# smartControllerDIP.net
KiCad netlist of a schematic drawn in Altium Designer
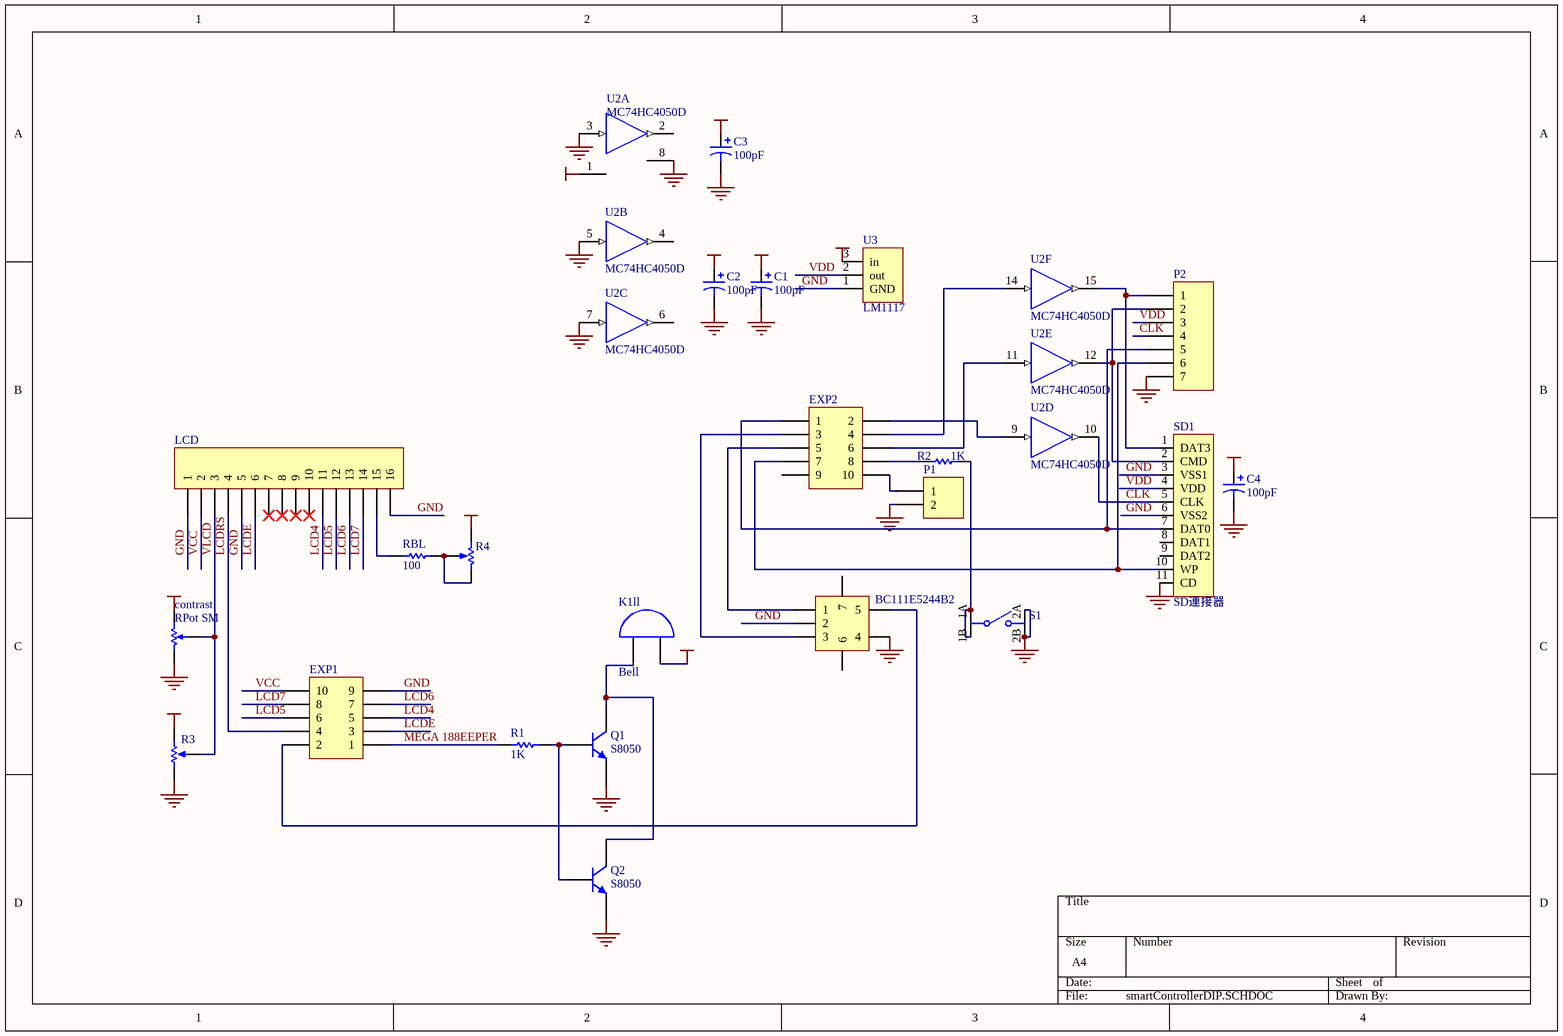
[diagram p0: smartControllerDIP.SCHDOC]

(export (version "E")
  (design (tool "Eeschema 10.0.6"))
  (components
    (comp (ref "BC111E5244B2")
      (value "上下數 編碼器")
      (footprint "上下數 編碼器")
      (libsource (lib "mydata") (part "上下數 編碼器"))
    )
    (comp (ref "C1")
      (value "100pF")
      (footprint "CC2012-0805")
      (description "Polarized Capacitor (Surface Mount)")
      (fields (field (name "Comment") "Cap Pol3") (field (name "PUBLISHER") "Altium Limited"))
      (libsource (lib "Miscellaneous Devices") (part "Cap Pol3"))
    )
    (comp (ref "C2")
      (value "100pF")
      (footprint "CC2012-0805")
      (description "Polarized Capacitor (Surface Mount)")
      (fields (field (name "Comment") "Cap Pol3") (field (name "PUBLISHER") "Altium Limited"))
      (libsource (lib "Miscellaneous Devices") (part "Cap Pol3"))
    )
    (comp (ref "C3")
      (value "100pF")
      (footprint "CC2012-0805")
      (description "Polarized Capacitor (Surface Mount)")
      (fields (field (name "Comment") "Cap Pol3") (field (name "PUBLISHER") "Altium Limited"))
      (libsource (lib "Miscellaneous Devices") (part "Cap Pol3"))
    )
    (comp (ref "C4")
      (value "100pF")
      (footprint "CC2012-0805")
      (description "Polarized Capacitor (Surface Mount)")
      (fields (field (name "Comment") "Cap Pol3") (field (name "PUBLISHER") "Altium Limited"))
      (libsource (lib "Miscellaneous Devices") (part "Cap Pol3"))
    )
    (comp (ref "contrast")
      (value "RPot SM")
      (footprint "POT4MM-2")
      (description "Square Trimming Potentiometer")
      (fields (field (name "PUBLISHER") "Altium Limited"))
      (libsource (lib "Miscellaneous Devices") (part "RPot SM"))
    )
    (comp (ref "EXP1")
      (value "Header 5X2")
      (footprint "10pin牛角公座")
      (description "Header, 5-Pin, Dual row")
      (fields (field (name "PUBLISHER") "Altium Limited"))
      (libsource (lib "Miscellaneous Connectors") (part "Header 5X2"))
    )
    (comp (ref "EXP2")
      (value "Header 5X2")
      (footprint "10pin牛角公座")
      (description "Header, 5-Pin, Dual row")
      (fields (field (name "PUBLISHER") "Altium Limited"))
      (libsource (lib "") (part "Header 5X2_1"))
    )
    (comp (ref "K1ll")
      (value "Bell")
      (footprint "speaker")
      (description "Electrical Bell")
      (fields (field (name "PUBLISHER") "Altium Limited"))
      (libsource (lib "Miscellaneous Devices") (part "Bell"))
    )
    (comp (ref "LCD")
      (value "Header 16")
      (footprint "HDR1X16")
      (description "Header, 16-Pin")
      (fields (field (name "PUBLISHER") "Altium Limited"))
      (libsource (lib "Miscellaneous Connectors") (part "Header 16"))
    )
    (comp (ref "P1")
      (value "Header 2")
      (footprint "HDR1X2")
      (description "Header, 2-Pin")
      (fields (field (name "PUBLISHER") "Altium Limited"))
      (libsource (lib "Miscellaneous Connectors") (part "Header 2"))
    )
    (comp (ref "P2")
      (value "Header 7")
      (footprint "HDR1X7")
      (description "Header, 7-Pin")
      (fields (field (name "PUBLISHER") "Altium Limited"))
      (libsource (lib "Miscellaneous Connectors") (part "Header 7"))
    )
    (comp (ref "Q1") (value "S8050") (footprint "sot-23") (libsource (lib "mydata") (part "S8050")))
    (comp (ref "Q2") (value "S8050") (footprint "A684") (libsource (lib "mydata") (part "A684")))
    (comp (ref "R1")
      (value "1K")
      (footprint "0805")
      (description "Resistor")
      (fields (field (name "Comment") "Res1") (field (name "PUBLISHER") "Altium Limited"))
      (libsource (lib "Miscellaneous Devices") (part "Res1"))
    )
    (comp (ref "R2")
      (value "1K")
      (footprint "0805")
      (description "Resistor")
      (fields (field (name "Comment") "Res1") (field (name "PUBLISHER") "Altium Limited"))
      (libsource (lib "Miscellaneous Devices") (part "Res1"))
    )
    (comp (ref "R3")
      (value "VR1")
      (footprint "mydata:VR1")
      (description "Potentiometer")
      (fields (field (name "PUBLISHER") "Altium Limited"))
      (libsource (lib "mydata") (part "VR1"))
    )
    (comp (ref "R4")
      (value "VR1")
      (footprint "mydata:VR1")
      (description "Potentiometer")
      (fields (field (name "PUBLISHER") "Altium Limited"))
      (libsource (lib "mydata") (part "VR1"))
    )
    (comp (ref "RBL")
      (value "100")
      (footprint "0805")
      (description "Resistor")
      (fields (field (name "Comment") "Res1") (field (name "PUBLISHER") "Altium Limited"))
      (libsource (lib "Miscellaneous Devices") (part "Res1"))
    )
    (comp (ref "S1")
      (value "SW DIP4")
      (footprint "mydata:SW DIP4")
      (description "Single-Pole, Single-Throw Switch")
      (fields (field (name "PUBLISHER") "Altium Limited"))
      (libsource (lib "mydata") (part "SW DIP4"))
    )
    (comp (ref "SD1") (value "SD連接器") (footprint "SD-4") (libsource (lib "mydata") (part "SD連接器")))
    (comp (ref "U2")
      (value "MC74HC4050D")
      (footprint "751B-03")
      (description "Hex Non-Inverting Buffer/Logic-Level Down Converter")
      (fields (field (name "PUBLISHER") "Altium Limited"))
      (libsource (lib "Motorola Logic Gate") (part "MC74HC4050D"))
    )
    (comp (ref "U3") (value "LM1117") (footprint "SOT-223") (libsource (lib "mydata") (part "LM1117")))
  )
  (nets
    (net (code "1") (name "/CLK") (class "Default")
      (node (ref "P2") (pin "4") (pinfunction "4_4") (pintype "passive"))
      (node (ref "SD1") (pin "5") (pinfunction "CLK_5") (pintype "passive"))
      (node (ref "U2") (pin "10") (pinfunction "Y_10") (pintype "output"))
    )
    (net (code "2") (name "/LCD4") (class "Default")
      (node (ref "EXP1") (pin "5") (pinfunction "5_5") (pintype "passive"))
      (node (ref "LCD") (pin "11") (pinfunction "11_11") (pintype "passive"))
    )
    (net (code "3") (name "/LCD5") (class "Default")
      (node (ref "EXP1") (pin "6") (pinfunction "6_6") (pintype "passive"))
      (node (ref "LCD") (pin "12") (pinfunction "12_12") (pintype "passive"))
    )
    (net (code "4") (name "/LCD6") (class "Default")
      (node (ref "EXP1") (pin "7") (pinfunction "7_7") (pintype "passive"))
      (node (ref "LCD") (pin "13") (pinfunction "13_13") (pintype "passive"))
    )
    (net (code "5") (name "/LCD7") (class "Default")
      (node (ref "EXP1") (pin "8") (pinfunction "8_8") (pintype "passive"))
      (node (ref "LCD") (pin "14") (pinfunction "14_14") (pintype "passive"))
    )
    (net (code "6") (name "/LCDE") (class "Default")
      (node (ref "EXP1") (pin "3") (pinfunction "3_3") (pintype "passive"))
      (node (ref "LCD") (pin "6") (pinfunction "6_6") (pintype "passive"))
    )
    (net (code "7") (name "/LCDRS") (class "Default")
      (node (ref "EXP1") (pin "4") (pinfunction "4_4") (pintype "passive"))
      (node (ref "LCD") (pin "4") (pinfunction "4_4") (pintype "passive"))
    )
    (net (code "8") (name "/MEGA 188EEPER") (class "Default")
      (node (ref "EXP1") (pin "1") (pinfunction "1_1") (pintype "passive"))
      (node (ref "R1") (pin "1") (pinfunction "1_1") (pintype "passive"))
    )
    (net (code "9") (name "/VLCD") (class "Default")
      (node (ref "LCD") (pin "3") (pinfunction "3_3") (pintype "passive"))
      (node (ref "R3") (pin "2") (pinfunction "TAP_2") (pintype "passive"))
      (node (ref "contrast") (pin "W") (pinfunction "W_W") (pintype "passive"))
    )
    (net (code "10") (name "GND") (class "Default")
      (node (ref "BC111E5244B2") (pin "2") (pinfunction "2_2") (pintype "passive"))
      (node (ref "BC111E5244B2") (pin "4") (pinfunction "4_4") (pintype "passive"))
      (node (ref "C1") (pin "2") (pinfunction "2_2") (pintype "passive"))
      (node (ref "C2") (pin "2") (pinfunction "2_2") (pintype "passive"))
      (node (ref "C3") (pin "2") (pinfunction "2_2") (pintype "passive"))
      (node (ref "C4") (pin "2") (pinfunction "2_2") (pintype "passive"))
      (node (ref "EXP1") (pin "9") (pinfunction "9_9") (pintype "passive"))
      (node (ref "LCD") (pin "1") (pinfunction "1_1") (pintype "passive"))
      (node (ref "LCD") (pin "16") (pinfunction "16_16") (pintype "passive"))
      (node (ref "LCD") (pin "5") (pinfunction "5_5") (pintype "passive"))
      (node (ref "P1") (pin "2") (pinfunction "2_2") (pintype "passive"))
      (node (ref "P2") (pin "7") (pinfunction "7_7") (pintype "passive"))
      (node (ref "Q1") (pin "2") (pinfunction "E_2") (pintype "passive"))
      (node (ref "Q2") (pin "1") (pinfunction "E_1") (pintype "passive"))
      (node (ref "R3") (pin "1") (pinfunction "TOP_1") (pintype "passive"))
      (node (ref "S1") (pin "2A") (pinfunction "2_2A") (pintype "passive"))
      (node (ref "S1") (pin "2B") (pinfunction "2_2B") (pintype "passive"))
      (node (ref "SD1") (pin "11") (pinfunction "CD_11") (pintype "passive"))
      (node (ref "SD1") (pin "3") (pinfunction "VSS1_3") (pintype "passive"))
      (node (ref "SD1") (pin "6") (pinfunction "VSS2_6") (pintype "passive"))
      (node (ref "U2") (pin "3") (pinfunction "A_3") (pintype "input"))
      (node (ref "U2") (pin "5") (pinfunction "A_5") (pintype "input"))
      (node (ref "U2") (pin "7") (pinfunction "A_7") (pintype "input"))
      (node (ref "U2") (pin "8") (pinfunction "GND_8") (pintype "power_in"))
      (node (ref "U3") (pin "1") (pinfunction "GND_1") (pintype "passive"))
      (node (ref "contrast") (pin "CW") (pinfunction "+_CW") (pintype "passive"))
    )
    (net (code "11") (name "Net-(BC111E5244B2-Pad1)") (class "Default")
      (node (ref "BC111E5244B2") (pin "1") (pinfunction "1_1") (pintype "passive"))
      (node (ref "EXP2") (pin "5") (pinfunction "5_5") (pintype "passive"))
    )
    (net (code "12") (name "Net-(BC111E5244B2-Pad3)") (class "Default")
      (node (ref "BC111E5244B2") (pin "3") (pinfunction "3_3") (pintype "passive"))
      (node (ref "EXP2") (pin "3") (pinfunction "3_3") (pintype "passive"))
    )
    (net (code "13") (name "Net-(BC111E5244B2-Pad5)") (class "Default")
      (node (ref "BC111E5244B2") (pin "5") (pinfunction "5_5") (pintype "passive"))
      (node (ref "EXP1") (pin "2") (pinfunction "2_2") (pintype "passive"))
    )
    (net (code "14") (name "Net-(EXP2-Pad8)") (class "Default")
      (node (ref "EXP2") (pin "8") (pinfunction "8_8") (pintype "passive"))
      (node (ref "R2") (pin "1") (pinfunction "1_1") (pintype "passive"))
    )
    (net (code "15") (name "Net-(EXP2-Pad10)") (class "Default")
      (node (ref "EXP2") (pin "10") (pinfunction "10_10") (pintype "passive"))
      (node (ref "P1") (pin "1") (pinfunction "1_1") (pintype "passive"))
    )
    (net (code "16") (name "Net-(K1ll-A)") (class "Default")
      (node (ref "K1ll") (pin "1") (pinfunction "A_1") (pintype "passive"))
      (node (ref "Q1") (pin "3") (pinfunction "C_3") (pintype "passive"))
      (node (ref "Q2") (pin "2") (pinfunction "C_2") (pintype "passive"))
    )
    (net (code "17") (name "Net-(LCD-Pad15)") (class "Default")
      (node (ref "LCD") (pin "15") (pinfunction "15_15") (pintype "passive"))
      (node (ref "RBL") (pin "1") (pinfunction "1_1") (pintype "passive"))
    )
    (net (code "18") (name "Net-(Q1-B)") (class "Default")
      (node (ref "Q1") (pin "1") (pinfunction "B_1") (pintype "passive"))
      (node (ref "Q2") (pin "3") (pinfunction "B_3") (pintype "passive"))
      (node (ref "R1") (pin "2") (pinfunction "2_2") (pintype "passive"))
    )
    (net (code "19") (name "Net-(R2-Pad2)") (class "Default")
      (node (ref "R2") (pin "2") (pinfunction "2_2") (pintype "passive"))
      (node (ref "S1") (pin "1A") (pinfunction "1_1A") (pintype "passive"))
      (node (ref "S1") (pin "1B") (pinfunction "1_1B") (pintype "passive"))
    )
    (net (code "20") (name "Net-(R4-TAP)") (class "Default")
      (node (ref "R4") (pin "1") (pinfunction "TOP_1") (pintype "passive"))
      (node (ref "R4") (pin "2") (pinfunction "TAP_2") (pintype "passive"))
      (node (ref "RBL") (pin "2") (pinfunction "2_2") (pintype "passive"))
    )
    (net (code "21") (name "Net-(SD1-CMD)") (class "Default")
      (node (ref "P2") (pin "2") (pinfunction "2_2") (pintype "passive"))
      (node (ref "SD1") (pin "2") (pinfunction "CMD_2") (pintype "passive"))
      (node (ref "U2") (pin "12") (pinfunction "Y_12") (pintype "output"))
    )
    (net (code "22") (name "Net-(SD1-DAT0)") (class "Default")
      (node (ref "EXP2") (pin "1") (pinfunction "1_1") (pintype "passive"))
      (node (ref "P2") (pin "5") (pinfunction "5_5") (pintype "passive"))
      (node (ref "SD1") (pin "7") (pinfunction "DAT0_7") (pintype "passive"))
    )
    (net (code "23") (name "Net-(SD1-DAT3)") (class "Default")
      (node (ref "P2") (pin "1") (pinfunction "1_1") (pintype "passive"))
      (node (ref "SD1") (pin "1") (pinfunction "DAT3_1") (pintype "passive"))
      (node (ref "U2") (pin "15") (pinfunction "Y_15") (pintype "output"))
    )
    (net (code "24") (name "Net-(SD1-WP)") (class "Default")
      (node (ref "EXP2") (pin "7") (pinfunction "7_7") (pintype "passive"))
      (node (ref "P2") (pin "6") (pinfunction "6_6") (pintype "passive"))
      (node (ref "SD1") (pin "10") (pinfunction "WP_10") (pintype "passive"))
    )
    (net (code "25") (name "Net-(U2D-A)") (class "Default")
      (node (ref "EXP2") (pin "2") (pinfunction "2_2") (pintype "passive"))
      (node (ref "U2") (pin "9") (pinfunction "A_9") (pintype "input"))
    )
    (net (code "26") (name "Net-(U2E-A)") (class "Default")
      (node (ref "EXP2") (pin "6") (pinfunction "6_6") (pintype "passive"))
      (node (ref "U2") (pin "11") (pinfunction "A_11") (pintype "input"))
    )
    (net (code "27") (name "Net-(U2F-A)") (class "Default")
      (node (ref "EXP2") (pin "4") (pinfunction "4_4") (pintype "passive"))
      (node (ref "U2") (pin "14") (pinfunction "A_14") (pintype "input"))
    )
    (net (code "28") (name "VCC") (class "Default")
      (node (ref "C1") (pin "1") (pinfunction "1_1") (pintype "passive"))
      (node (ref "EXP1") (pin "10") (pinfunction "10_10") (pintype "passive"))
      (node (ref "K1ll") (pin "2") (pinfunction "B_2") (pintype "passive"))
      (node (ref "LCD") (pin "2") (pinfunction "2_2") (pintype "passive"))
      (node (ref "R3") (pin "3") (pinfunction "BOT_3") (pintype "passive"))
      (node (ref "R4") (pin "3") (pinfunction "BOT_3") (pintype "passive"))
      (node (ref "U3") (pin "3") (pinfunction "in_3") (pintype "passive"))
      (node (ref "contrast") (pin "CCW") (pinfunction "-_CCW") (pintype "passive"))
    )
    (net (code "29") (name "VDD") (class "Default")
      (node (ref "C2") (pin "1") (pinfunction "1_1") (pintype "passive"))
      (node (ref "C3") (pin "1") (pinfunction "1_1") (pintype "passive"))
      (node (ref "C4") (pin "1") (pinfunction "1_1") (pintype "passive"))
      (node (ref "P2") (pin "3") (pinfunction "3_3") (pintype "passive"))
      (node (ref "SD1") (pin "4") (pinfunction "VDD_4") (pintype "passive"))
      (node (ref "U2") (pin "1") (pinfunction "VDD_1") (pintype "power_in"))
      (node (ref "U3") (pin "2") (pinfunction "out_2") (pintype "passive"))
    )
    (net (code "30") (name "unconnected-(BC111E5244B2-Pad6)") (class "Default")
      (node (ref "BC111E5244B2") (pin "6") (pinfunction "6_6") (pintype "passive"))
    )
    (net (code "31") (name "unconnected-(BC111E5244B2-Pad7)") (class "Default")
      (node (ref "BC111E5244B2") (pin "7") (pinfunction "7_7") (pintype "passive"))
    )
    (net (code "32") (name "unconnected-(EXP2-Pad9)") (class "Default")
      (node (ref "EXP2") (pin "9") (pinfunction "9_9") (pintype "passive"))
    )
    (net (code "33") (name "unconnected-(LCD-Pad7)") (class "Default")
      (node (ref "LCD") (pin "7") (pinfunction "7_7") (pintype "passive+no_connect"))
    )
    (net (code "34") (name "unconnected-(LCD-Pad8)") (class "Default")
      (node (ref "LCD") (pin "8") (pinfunction "8_8") (pintype "passive+no_connect"))
    )
    (net (code "35") (name "unconnected-(LCD-Pad9)") (class "Default")
      (node (ref "LCD") (pin "9") (pinfunction "9_9") (pintype "passive+no_connect"))
    )
    (net (code "36") (name "unconnected-(LCD-Pad10)") (class "Default")
      (node (ref "LCD") (pin "10") (pinfunction "10_10") (pintype "passive+no_connect"))
    )
    (net (code "37") (name "unconnected-(SD1-DAT1-Pad8)") (class "Default")
      (node (ref "SD1") (pin "8") (pinfunction "DAT1_8") (pintype "passive"))
    )
    (net (code "38") (name "unconnected-(SD1-DAT2-Pad9)") (class "Default")
      (node (ref "SD1") (pin "9") (pinfunction "DAT2_9") (pintype "passive"))
    )
    (net (code "39") (name "unconnected-(U2A-Y-Pad2)") (class "Default")
      (node (ref "U2") (pin "2") (pinfunction "Y_2") (pintype "output"))
    )
    (net (code "40") (name "unconnected-(U2B-Y-Pad4)") (class "Default")
      (node (ref "U2") (pin "4") (pinfunction "Y_4") (pintype "output"))
    )
    (net (code "41") (name "unconnected-(U2C-Y-Pad6)") (class "Default")
      (node (ref "U2") (pin "6") (pinfunction "Y_6") (pintype "output"))
    )
  )
)
